# LED_Driver.net
KiCad netlist of a schematic drawn in Altium Designer
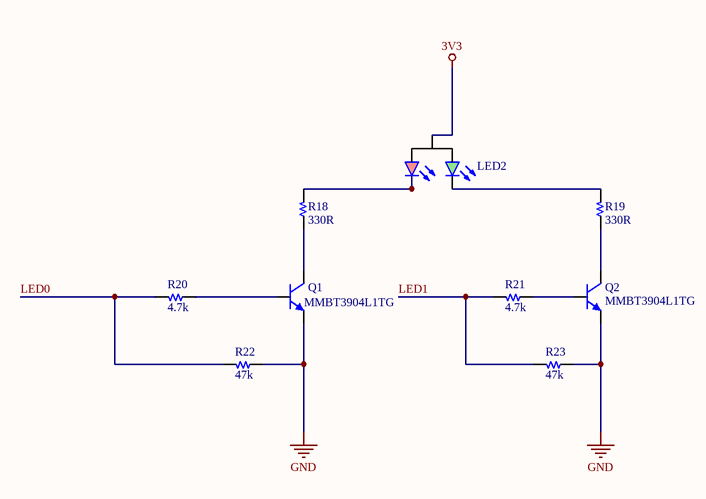
[diagram p0: LED_Driver.SchDoc]

(export (version "E")
  (design (tool "Eeschema 10.0.6"))
  (components
    (comp (ref "LED2")
      (value "Led 3pin 2color")
      (footprint "LED 3PIN 2COLOR 5MM")
      (description "Typical LED 3-pin 2-color")
      (libsource (lib "led") (part "Led 3pin 2color"))
    )
    (comp (ref "Q1")
      (value "MMBT3904L1TG")
      (footprint "SOT-23")
      (description "NPN Bipolar Transistor")
      (libsource (lib "chipfc_libs") (part "Transistor NPN"))
    )
    (comp (ref "Q2")
      (value "MMBT3904L1TG")
      (footprint "SOT-23")
      (description "NPN Bipolar Transistor")
      (libsource (lib "chipfc_libs") (part "Transistor NPN"))
    )
    (comp (ref "R18")
      (value "330R")
      (footprint "R 0805")
      (description "Resistor")
      (libsource (lib "chipfc_libs") (part "Resistor"))
    )
    (comp (ref "R19")
      (value "330R")
      (footprint "R 0805")
      (description "Resistor")
      (libsource (lib "chipfc_libs") (part "Resistor"))
    )
    (comp (ref "R20")
      (value "4.7k")
      (footprint "R 0805")
      (description "Resistor")
      (libsource (lib "chipfc_libs") (part "Resistor"))
    )
    (comp (ref "R21")
      (value "4.7k")
      (footprint "R 0805")
      (description "Resistor")
      (libsource (lib "chipfc_libs") (part "Resistor"))
    )
    (comp (ref "R22")
      (value "47k")
      (footprint "R 0805")
      (description "Resistor")
      (libsource (lib "chipfc_libs") (part "Resistor"))
    )
    (comp (ref "R23")
      (value "47k")
      (footprint "R 0805")
      (description "Resistor")
      (libsource (lib "chipfc_libs") (part "Resistor"))
    )
  )
  (nets
    (net (code "1") (name "/LED0") (class "Default")
      (node (ref "R20") (pin "2") (pinfunction "2_2") (pintype "passive"))
      (node (ref "R22") (pin "2") (pinfunction "2_2") (pintype "passive"))
    )
    (net (code "2") (name "/LED1") (class "Default")
      (node (ref "R21") (pin "2") (pinfunction "2_2") (pintype "passive"))
      (node (ref "R23") (pin "2") (pinfunction "2_2") (pintype "passive"))
    )
    (net (code "3") (name "3V3") (class "Default")
      (node (ref "LED2") (pin "2") (pinfunction "A_2") (pintype "passive"))
    )
    (net (code "4") (name "GND") (class "Default")
      (node (ref "Q1") (pin "2") (pinfunction "E_2") (pintype "passive"))
      (node (ref "Q2") (pin "2") (pinfunction "E_2") (pintype "passive"))
      (node (ref "R22") (pin "1") (pinfunction "1_1") (pintype "passive"))
      (node (ref "R23") (pin "1") (pinfunction "1_1") (pintype "passive"))
    )
    (net (code "5") (name "Net-(LED2-RK)") (class "Default")
      (node (ref "LED2") (pin "1") (pinfunction "RK_1") (pintype "passive"))
      (node (ref "R18") (pin "2") (pinfunction "2_2") (pintype "passive"))
    )
    (net (code "6") (name "Net-(LED2-YK)") (class "Default")
      (node (ref "LED2") (pin "3") (pinfunction "YK_3") (pintype "passive"))
      (node (ref "R19") (pin "2") (pinfunction "2_2") (pintype "passive"))
    )
    (net (code "7") (name "Net-(Q1-B)") (class "Default")
      (node (ref "Q1") (pin "1") (pinfunction "B_1") (pintype "passive"))
      (node (ref "R20") (pin "1") (pinfunction "1_1") (pintype "passive"))
    )
    (net (code "8") (name "Net-(Q1-C)") (class "Default")
      (node (ref "Q1") (pin "3") (pinfunction "C_3") (pintype "passive"))
      (node (ref "R18") (pin "1") (pinfunction "1_1") (pintype "passive"))
    )
    (net (code "9") (name "Net-(Q2-B)") (class "Default")
      (node (ref "Q2") (pin "1") (pinfunction "B_1") (pintype "passive"))
      (node (ref "R21") (pin "1") (pinfunction "1_1") (pintype "passive"))
    )
    (net (code "10") (name "Net-(Q2-C)") (class "Default")
      (node (ref "Q2") (pin "3") (pinfunction "C_3") (pintype "passive"))
      (node (ref "R19") (pin "1") (pinfunction "1_1") (pintype "passive"))
    )
  )
)
